# 2022-11-04_ESP32-Cseries_Riser_v1_0.net
KiCad netlist of a schematic drawn in EasyEDA
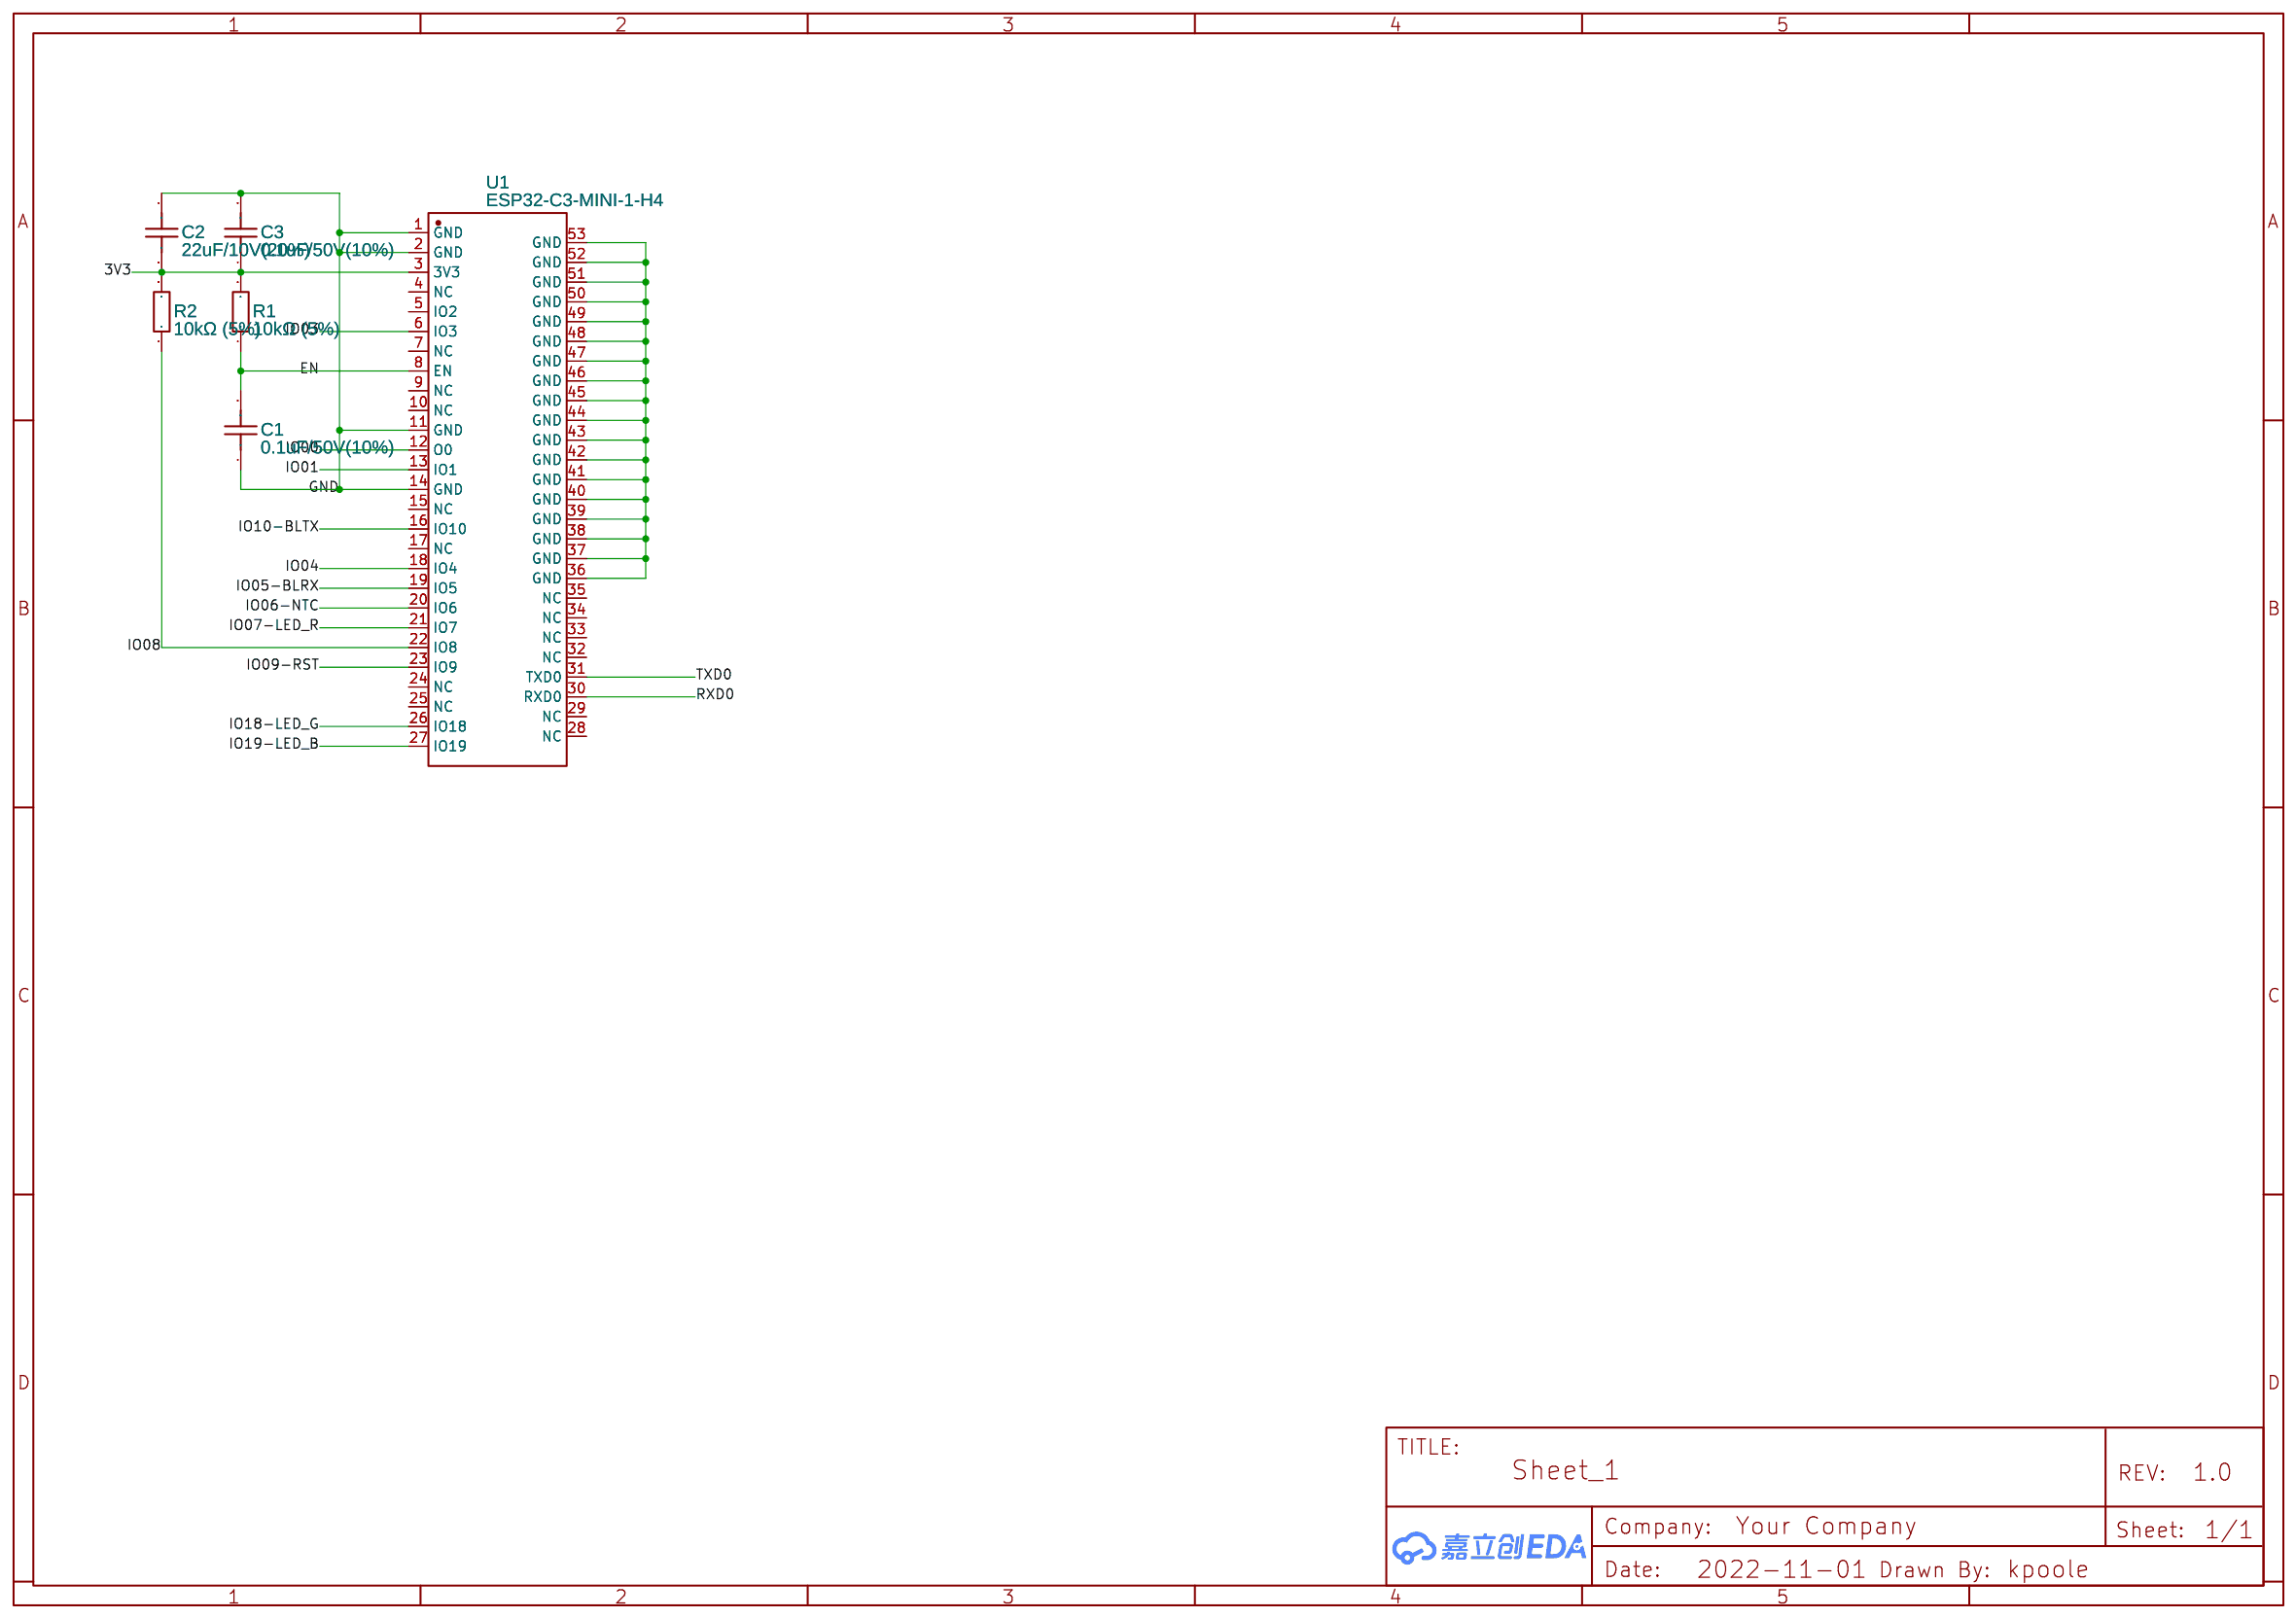
[diagram p0: schematic sheet]

(export (version "E")
  (design (tool "Eeschema 10.0.6"))
  (components
    (comp (ref "C1")
      (value "0.1uF/50V(10%)")
      (fields
        (field (name "BOM_Manufacturer Part") "0603BB104K500NGT")
        (field (name "BOM_Supplier Part") "C2168571")
      )
      (libsource (lib "") (part "0603BB104K500NGT"))
    )
    (comp (ref "C2")
      (value "22uF/10V(20%)")
      (fields
        (field (name "BOM_Manufacturer Part") "CL10A226MP8NUNE")
        (field (name "BOM_Supplier Part") "C86295")
      )
      (libsource (lib "") (part "CL10A226MP8NUNE"))
    )
    (comp (ref "C3")
      (value "0.1uF/50V(10%)")
      (fields
        (field (name "BOM_Manufacturer Part") "CAP-SMD-0603-10uF-50V-10%")
        (field (name "BOM_Supplier Part") "C9900006127")
      )
      (libsource (lib "") (part "CAP-SMD-0603-10UF-50V-10%"))
    )
    (comp (ref "R1")
      (value "10kΩ (5%)")
      (fields
        (field (name "BOM_Manufacturer Part") "RK73B2ATTD103J")
        (field (name "BOM_Supplier Part") "C159912")
      )
      (libsource (lib "") (part "RK73B2ATTD103J"))
    )
    (comp (ref "R2")
      (value "10kΩ (5%)")
      (fields
        (field (name "BOM_Manufacturer Part") "RK73B2ATTD103J")
        (field (name "BOM_Supplier Part") "C159912")
      )
      (libsource (lib "") (part "RK73B2ATTD103J"))
    )
    (comp (ref "U1")
      (value "ESP32-C3-MINI-1-H4")
      (fields (field (name "BOM_Supplier Part") "C2935306"))
      (libsource (lib "") (part "ESP32-C3-MINI-1-H4"))
    )
  )
  (nets
    (net (code "1") (name "/3V3") (class "Default")
      (node (ref "C2") (pin "2") (pinfunction "2_2") (pintype "unspecified"))
      (node (ref "C3") (pin "1") (pinfunction "1_1") (pintype "unspecified"))
      (node (ref "R1") (pin "2") (pinfunction "2_2") (pintype "unspecified"))
      (node (ref "R2") (pin "2") (pinfunction "2_2") (pintype "unspecified"))
      (node (ref "U1") (pin "3") (pinfunction "3V3_3") (pintype "unspecified"))
    )
    (net (code "2") (name "/EN") (class "Default")
      (node (ref "C1") (pin "2") (pinfunction "2_2") (pintype "unspecified"))
      (node (ref "R1") (pin "1") (pinfunction "1_1") (pintype "unspecified"))
      (node (ref "U1") (pin "8") (pinfunction "EN_8") (pintype "unspecified"))
    )
    (net (code "3") (name "/GND") (class "Default")
      (node (ref "C1") (pin "1") (pinfunction "1_1") (pintype "unspecified"))
      (node (ref "C2") (pin "1") (pinfunction "1_1") (pintype "unspecified"))
      (node (ref "C3") (pin "2") (pinfunction "2_2") (pintype "unspecified"))
      (node (ref "U1") (pin "1") (pinfunction "GND_1") (pintype "unspecified"))
      (node (ref "U1") (pin "11") (pinfunction "GND_11") (pintype "unspecified"))
      (node (ref "U1") (pin "14") (pinfunction "GND_14") (pintype "unspecified"))
      (node (ref "U1") (pin "2") (pinfunction "GND_2") (pintype "unspecified"))
    )
    (net (code "4") (name "/IO00") (class "Default")
      (node (ref "U1") (pin "12") (pinfunction "O0_12") (pintype "unspecified"))
    )
    (net (code "5") (name "/IO01") (class "Default")
      (node (ref "U1") (pin "13") (pinfunction "IO1_13") (pintype "unspecified"))
    )
    (net (code "6") (name "/IO03") (class "Default")
      (node (ref "U1") (pin "6") (pinfunction "IO3_6") (pintype "unspecified"))
    )
    (net (code "7") (name "/IO04") (class "Default")
      (node (ref "U1") (pin "18") (pinfunction "IO4_18") (pintype "unspecified"))
    )
    (net (code "8") (name "/IO05-BLRX") (class "Default")
      (node (ref "U1") (pin "19") (pinfunction "IO5_19") (pintype "unspecified"))
    )
    (net (code "9") (name "/IO06-NTC") (class "Default")
      (node (ref "U1") (pin "20") (pinfunction "IO6_20") (pintype "unspecified"))
    )
    (net (code "10") (name "/IO07-LED_R") (class "Default")
      (node (ref "U1") (pin "21") (pinfunction "IO7_21") (pintype "unspecified"))
    )
    (net (code "11") (name "/IO08") (class "Default")
      (node (ref "R2") (pin "1") (pinfunction "1_1") (pintype "unspecified"))
      (node (ref "U1") (pin "22") (pinfunction "IO8_22") (pintype "unspecified"))
    )
    (net (code "12") (name "/IO09-RST") (class "Default")
      (node (ref "U1") (pin "23") (pinfunction "IO9_23") (pintype "unspecified"))
    )
    (net (code "13") (name "/IO10-BLTX") (class "Default")
      (node (ref "U1") (pin "16") (pinfunction "IO10_16") (pintype "unspecified"))
    )
    (net (code "14") (name "/IO18-LED_G") (class "Default")
      (node (ref "U1") (pin "26") (pinfunction "IO18_26") (pintype "unspecified"))
    )
    (net (code "15") (name "/IO19-LED_B") (class "Default")
      (node (ref "U1") (pin "27") (pinfunction "IO19_27") (pintype "unspecified"))
    )
    (net (code "16") (name "/RXD0") (class "Default")
      (node (ref "U1") (pin "30") (pinfunction "RXD0_30") (pintype "unspecified"))
    )
    (net (code "17") (name "/TXD0") (class "Default")
      (node (ref "U1") (pin "31") (pinfunction "TXD0_31") (pintype "unspecified"))
    )
    (net (code "18") (name "Net-(U1-GND-Pad36)") (class "Default")
      (node (ref "U1") (pin "36") (pinfunction "GND_36") (pintype "unspecified"))
      (node (ref "U1") (pin "37") (pinfunction "GND_37") (pintype "unspecified"))
      (node (ref "U1") (pin "38") (pinfunction "GND_38") (pintype "unspecified"))
      (node (ref "U1") (pin "39") (pinfunction "GND_39") (pintype "unspecified"))
      (node (ref "U1") (pin "40") (pinfunction "GND_40") (pintype "unspecified"))
      (node (ref "U1") (pin "41") (pinfunction "GND_41") (pintype "unspecified"))
      (node (ref "U1") (pin "42") (pinfunction "GND_42") (pintype "unspecified"))
      (node (ref "U1") (pin "43") (pinfunction "GND_43") (pintype "unspecified"))
      (node (ref "U1") (pin "44") (pinfunction "GND_44") (pintype "unspecified"))
      (node (ref "U1") (pin "45") (pinfunction "GND_45") (pintype "unspecified"))
      (node (ref "U1") (pin "46") (pinfunction "GND_46") (pintype "unspecified"))
      (node (ref "U1") (pin "47") (pinfunction "GND_47") (pintype "unspecified"))
      (node (ref "U1") (pin "48") (pinfunction "GND_48") (pintype "unspecified"))
      (node (ref "U1") (pin "49") (pinfunction "GND_49") (pintype "unspecified"))
      (node (ref "U1") (pin "50") (pinfunction "GND_50") (pintype "unspecified"))
      (node (ref "U1") (pin "51") (pinfunction "GND_51") (pintype "unspecified"))
      (node (ref "U1") (pin "52") (pinfunction "GND_52") (pintype "unspecified"))
      (node (ref "U1") (pin "53") (pinfunction "GND_53") (pintype "unspecified"))
    )
    (net (code "19") (name "unconnected-(U1-IO2-Pad5)") (class "Default")
      (node (ref "U1") (pin "5") (pinfunction "IO2_5") (pintype "unspecified"))
    )
    (net (code "20") (name "unconnected-(U1-NC-Pad4)") (class "Default")
      (node (ref "U1") (pin "4") (pinfunction "NC_4") (pintype "unspecified"))
    )
    (net (code "21") (name "unconnected-(U1-NC-Pad7)") (class "Default")
      (node (ref "U1") (pin "7") (pinfunction "NC_7") (pintype "unspecified"))
    )
    (net (code "22") (name "unconnected-(U1-NC-Pad9)") (class "Default")
      (node (ref "U1") (pin "9") (pinfunction "NC_9") (pintype "unspecified"))
    )
    (net (code "23") (name "unconnected-(U1-NC-Pad10)") (class "Default")
      (node (ref "U1") (pin "10") (pinfunction "NC_10") (pintype "unspecified"))
    )
    (net (code "24") (name "unconnected-(U1-NC-Pad15)") (class "Default")
      (node (ref "U1") (pin "15") (pinfunction "NC_15") (pintype "unspecified"))
    )
    (net (code "25") (name "unconnected-(U1-NC-Pad17)") (class "Default")
      (node (ref "U1") (pin "17") (pinfunction "NC_17") (pintype "unspecified"))
    )
    (net (code "26") (name "unconnected-(U1-NC-Pad24)") (class "Default")
      (node (ref "U1") (pin "24") (pinfunction "NC_24") (pintype "unspecified"))
    )
    (net (code "27") (name "unconnected-(U1-NC-Pad25)") (class "Default")
      (node (ref "U1") (pin "25") (pinfunction "NC_25") (pintype "unspecified"))
    )
    (net (code "28") (name "unconnected-(U1-NC-Pad28)") (class "Default")
      (node (ref "U1") (pin "28") (pinfunction "NC_28") (pintype "unspecified"))
    )
    (net (code "29") (name "unconnected-(U1-NC-Pad29)") (class "Default")
      (node (ref "U1") (pin "29") (pinfunction "NC_29") (pintype "unspecified"))
    )
    (net (code "30") (name "unconnected-(U1-NC-Pad32)") (class "Default")
      (node (ref "U1") (pin "32") (pinfunction "NC_32") (pintype "unspecified"))
    )
    (net (code "31") (name "unconnected-(U1-NC-Pad33)") (class "Default")
      (node (ref "U1") (pin "33") (pinfunction "NC_33") (pintype "unspecified"))
    )
    (net (code "32") (name "unconnected-(U1-NC-Pad34)") (class "Default")
      (node (ref "U1") (pin "34") (pinfunction "NC_34") (pintype "unspecified"))
    )
    (net (code "33") (name "unconnected-(U1-NC-Pad35)") (class "Default")
      (node (ref "U1") (pin "35") (pinfunction "NC_35") (pintype "unspecified"))
    )
  )
)
